# TLE5012_V1_2.net
KiCad netlist of a schematic drawn in Altium Designer
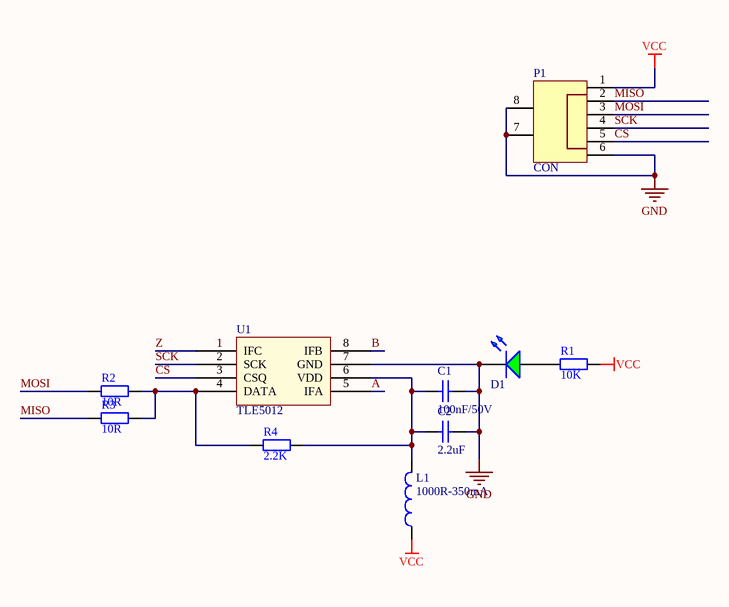
[diagram p0: TLE5012_V1.2.SchDoc]

(export (version "E")
  (design (tool "Eeschema 10.0.6"))
  (components
    (comp (ref "C1")
      (value "100nF/50V")
      (footprint "0402_C")
      (description "Capacitor")
      (fields (field (name "PUBLISHER") "Altium Limited"))
      (libsource (lib "Miscellaneous Devices") (part "Cap"))
    )
    (comp (ref "C2")
      (value "2.2uF")
      (footprint "0402_C")
      (description "Capacitor")
      (fields (field (name "PUBLISHER") "Altium Limited"))
      (libsource (lib "Miscellaneous Devices") (part "Cap"))
    )
    (comp (ref "D1")
      (value "0603_D-CL-0603 URC-RED")
      (footprint "0603_D")
      (description "LED")
      (libsource (lib "LED") (part "LED"))
    )
    (comp (ref "L1")
      (value "1000R-350mA")
      (footprint "0402_L")
      (description "Inductor")
      (fields (field (name "PUBLISHER") "Altium Limited"))
      (libsource (lib "Miscellaneous Devices") (part "Inductor"))
    )
    (comp (ref "P1") (value "CON") (footprint "BM06B-GHS-TBT(TOP)") (libsource (lib "CON-6") (part "CON-6")))
    (comp (ref "R1")
      (value "10K")
      (footprint "0402_R")
      (description "Resistor")
      (fields (field (name "PUBLISHER") "Altium Limited"))
      (libsource (lib "Miscellaneous Devices") (part "Res2"))
    )
    (comp (ref "R2")
      (value "10R")
      (footprint "0402_R")
      (description "Resistor")
      (fields (field (name "PUBLISHER") "Altium Limited"))
      (libsource (lib "Miscellaneous Devices") (part "Res2"))
    )
    (comp (ref "R3")
      (value "10R")
      (footprint "0402_R")
      (description "Resistor")
      (fields (field (name "PUBLISHER") "Altium Limited"))
      (libsource (lib "Miscellaneous Devices") (part "Res2"))
    )
    (comp (ref "R4")
      (value "2.2K")
      (footprint "0402_R")
      (description "Resistor")
      (fields (field (name "PUBLISHER") "Altium Limited"))
      (libsource (lib "Miscellaneous Devices") (part "Res2"))
    )
    (comp (ref "U1") (value "TLE5012") (footprint "SOP-8") (libsource (lib "TLE5012") (part "TLE5012")))
  )
  (nets
    (net (code "1") (name "/A") (class "Default")
      (node (ref "U1") (pin "5") (pinfunction "IFA_5") (pintype "passive"))
    )
    (net (code "2") (name "/B") (class "Default")
      (node (ref "U1") (pin "8") (pinfunction "IFB_8") (pintype "passive"))
    )
    (net (code "3") (name "/CS") (class "Default")
      (node (ref "P1") (pin "5") (pintype "passive"))
      (node (ref "U1") (pin "3") (pinfunction "CSQ_3") (pintype "passive"))
    )
    (net (code "4") (name "/MISO") (class "Default")
      (node (ref "P1") (pin "2") (pintype "passive"))
      (node (ref "R3") (pin "1") (pinfunction "1_1") (pintype "passive"))
    )
    (net (code "5") (name "/MOSI") (class "Default")
      (node (ref "P1") (pin "3") (pintype "passive"))
      (node (ref "R2") (pin "1") (pinfunction "1_1") (pintype "passive"))
    )
    (net (code "6") (name "/SCK") (class "Default")
      (node (ref "P1") (pin "4") (pintype "passive"))
      (node (ref "U1") (pin "2") (pinfunction "SCK_2") (pintype "passive"))
    )
    (net (code "7") (name "/Z") (class "Default")
      (node (ref "U1") (pin "1") (pinfunction "IFC_1") (pintype "passive"))
    )
    (net (code "8") (name "GND") (class "Default")
      (node (ref "C1") (pin "2") (pinfunction "2_2") (pintype "passive"))
      (node (ref "C2") (pin "2") (pinfunction "2_2") (pintype "passive"))
      (node (ref "D1") (pin "2") (pinfunction "K_2") (pintype "passive"))
      (node (ref "P1") (pin "6") (pintype "passive"))
      (node (ref "P1") (pin "7") (pintype "passive"))
      (node (ref "P1") (pin "8") (pintype "passive"))
      (node (ref "U1") (pin "7") (pinfunction "GND_7") (pintype "passive"))
    )
    (net (code "9") (name "Net-(D1-A)") (class "Default")
      (node (ref "D1") (pin "1") (pinfunction "A_1") (pintype "passive"))
      (node (ref "R1") (pin "1") (pinfunction "1_1") (pintype "passive"))
    )
    (net (code "10") (name "Net-(U1-DATA)") (class "Default")
      (node (ref "R2") (pin "2") (pinfunction "2_2") (pintype "passive"))
      (node (ref "R3") (pin "2") (pinfunction "2_2") (pintype "passive"))
      (node (ref "R4") (pin "1") (pinfunction "1_1") (pintype "passive"))
      (node (ref "U1") (pin "4") (pinfunction "DATA_4") (pintype "passive"))
    )
    (net (code "11") (name "Net-(U1-VDD)") (class "Default")
      (node (ref "C1") (pin "1") (pinfunction "1_1") (pintype "passive"))
      (node (ref "C2") (pin "1") (pinfunction "1_1") (pintype "passive"))
      (node (ref "L1") (pin "2") (pinfunction "2_2") (pintype "passive"))
      (node (ref "R4") (pin "2") (pinfunction "2_2") (pintype "passive"))
      (node (ref "U1") (pin "6") (pinfunction "VDD_6") (pintype "passive"))
    )
    (net (code "12") (name "VCC") (class "Default")
      (node (ref "L1") (pin "1") (pinfunction "1_1") (pintype "passive"))
      (node (ref "P1") (pin "1") (pintype "passive"))
      (node (ref "R1") (pin "2") (pinfunction "2_2") (pintype "passive"))
    )
  )
)
